# Brightside_Telemetry_RC_rev2.net
KiCad netlist of a schematic drawn in Altium Designer
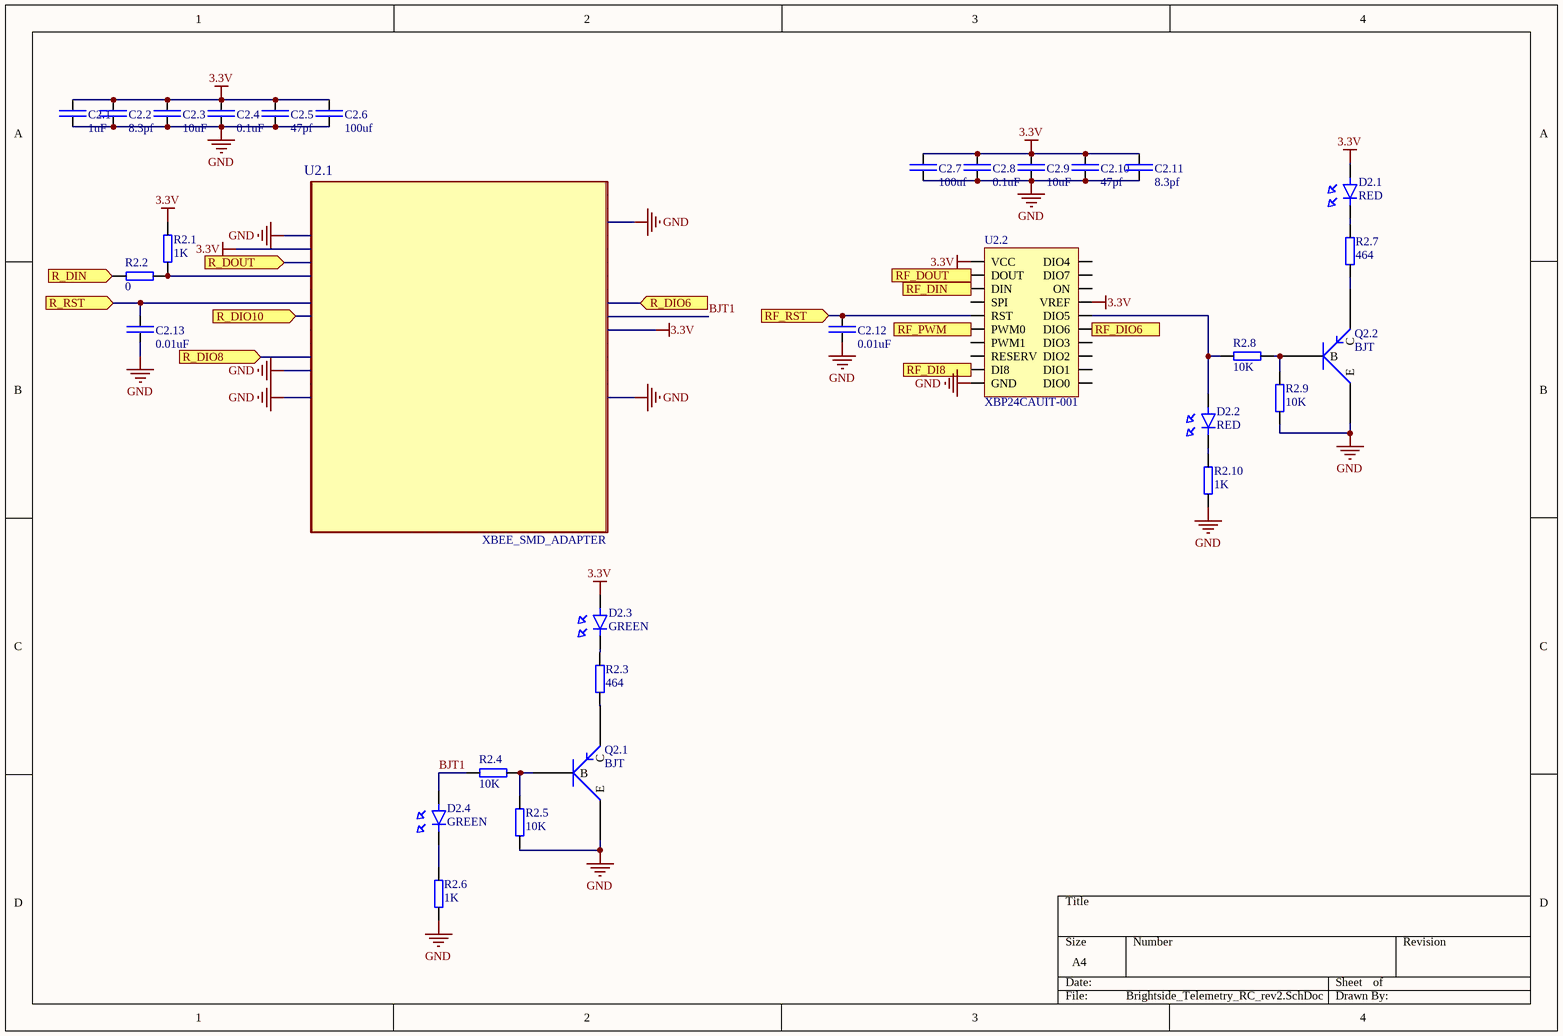
[diagram p0: Brightside_Telemetry_RC_rev2.SchDoc]

(export (version "E")
  (design (tool "Eeschema 10.0.6"))
  (components
    (comp (ref "C2.1")
      (value "1uF")
      (footprint "C0805")
      (description "Cap Ceramic 1uF 25V X7R 10% SMD 0805 125C T/R")
      (fields
        (field (name "MANUFACTURER") "Samsung")
        (field (name "MANUFACTURER PART NUMBER") "CL21B105KAFNNNE")
      )
      (libsource (lib "Capacitors") (part "CL21B105KAFNNNE"))
    )
    (comp (ref "C2.2")
      (value "8.3pf")
      (footprint "0603")
      (description "CAP CER RF 8.3PF 250V +/-0.1 PF")
      (fields
        (field (name "MANUFACTURER") "KEMET")
        (field (name "MANUFACTURER PART NUMBER") "CBR06C839BAGAC")
      )
      (libsource (lib "schem_lib") (part "CBR06C839BAGAC"))
    )
    (comp (ref "C2.3")
      (value "10uF")
      (footprint "C0805")
      (description "CAP CER 10UF 10V X5R 0805")
      (fields
        (field (name "MANUFACTURER") "Samsung")
        (field (name "MANUFACTURER PART NUMBER") "CL21B105KAFNNNE")
      )
      (libsource (lib "Capacitors") (part "C0805C106K8PACTU"))
    )
    (comp (ref "C2.4")
      (value "0.1uF")
      (footprint "0805")
      (description "Cap Ceramic 0.1uF 50V X7R 20% SMD 0805 125C Paper T/R")
      (fields
        (field (name "MANUFACTURER") "Samsung")
        (field (name "MANUFACTURER PART NUMBER") "CL21B104MBCNNNC")
      )
      (libsource (lib "Capacitors") (part "CL21B104MBCNNNC"))
    )
    (comp (ref "C2.5")
      (value "47pf")
      (footprint "0603")
      (description "CAP CER 47PF 100V C0G/NP0 0603")
      (fields
        (field (name "MANUFACTURER") "KEMET")
        (field (name "MANUFACTURER PART NUMBER") "C0603C470J1GACTU")
      )
      (libsource (lib "schem_lib") (part "C0603C470J1GACTU"))
    )
    (comp (ref "C2.6")
      (value "100uf")
      (footprint "1206")
      (description "Cap Ceramic 100uF 6.3V X5R 20% SMD 1206 85°C Embossed T/R")
      (fields
        (field (name "MANUFACTURER") "Murata")
        (field (name "MANUFACTURER PART NUMBER") "GRM21BR60G107ME15L")
      )
      (libsource (lib "schem_lib") (part "GRM21BR60G107ME15L"))
    )
    (comp (ref "C2.7")
      (value "100uf")
      (footprint "1206")
      (description "Cap Ceramic 100uF 6.3V X5R 20% SMD 1206 85°C Embossed T/R")
      (fields
        (field (name "MANUFACTURER") "Murata")
        (field (name "MANUFACTURER PART NUMBER") "GRM21BR60G107ME15L")
      )
      (libsource (lib "schem_lib") (part "GRM21BR60G107ME15L"))
    )
    (comp (ref "C2.8")
      (value "0.1uF")
      (footprint "0805")
      (description "Cap Ceramic 0.1uF 50V X7R 20% SMD 0805 125C Paper T/R")
      (fields
        (field (name "MANUFACTURER") "Samsung")
        (field (name "MANUFACTURER PART NUMBER") "CL21B104MBCNNNC")
      )
      (libsource (lib "Capacitors") (part "CL21B104MBCNNNC"))
    )
    (comp (ref "C2.9")
      (value "10uF")
      (footprint "C0805")
      (description "CAP CER 10UF 10V X5R 0805")
      (fields
        (field (name "MANUFACTURER") "Samsung")
        (field (name "MANUFACTURER PART NUMBER") "CL21B105KAFNNNE")
      )
      (libsource (lib "Capacitors") (part "C0805C106K8PACTU"))
    )
    (comp (ref "C2.10")
      (value "47pf")
      (footprint "0603")
      (description "CAP CER 47PF 100V C0G/NP0 0603")
      (fields
        (field (name "MANUFACTURER") "KEMET")
        (field (name "MANUFACTURER PART NUMBER") "C0603C470J1GACTU")
      )
      (libsource (lib "schem_lib") (part "C0603C470J1GACTU"))
    )
    (comp (ref "C2.11")
      (value "8.3pf")
      (footprint "0603")
      (description "CAP CER RF 8.3PF 250V +/-0.1 PF")
      (fields
        (field (name "MANUFACTURER") "KEMET")
        (field (name "MANUFACTURER PART NUMBER") "CBR06C839BAGAC")
      )
      (libsource (lib "schem_lib") (part "CBR06C839BAGAC"))
    )
    (comp (ref "C2.12")
      (value "0.01uF")
      (footprint "0805")
      (description "Cap Ceramic 0.01uF 100V X7R 10% SMD 0805 125C T/R")
      (fields
        (field (name "MANUFACTURER") "KEMET")
        (field (name "MANUFACTURER PART NUMBER") "C0805C103K1RAC7210")
      )
      (libsource (lib "Capacitors") (part "C0805C103K1RAC7210"))
    )
    (comp (ref "C2.13")
      (value "0.01uF")
      (footprint "0805")
      (description "Cap Ceramic 0.01uF 100V X7R 10% SMD 0805 125C T/R")
      (fields
        (field (name "MANUFACTURER") "KEMET")
        (field (name "MANUFACTURER PART NUMBER") "C0805C103K1RAC7210")
      )
      (libsource (lib "Capacitors") (part "C0805C103K1RAC7210"))
    )
    (comp (ref "D2.1")
      (value "RED")
      (footprint "0603 LED")
      (description "WURTH ELEKTRONIK - 150060RS75000 - LED, Red, 625 nm, 2 V, 30 mA, 250 mcd RoHS Compliant: Yes")
      (fields
        (field (name "MANUFACTURER") "Wurth Electronics")
        (field (name "MANUFACTURER PART NUMBER") "150060RS75000")
      )
      (libsource (lib "Indication & Control") (part "150060RS75000"))
    )
    (comp (ref "D2.2")
      (value "RED")
      (footprint "0603 LED")
      (description "WURTH ELEKTRONIK - 150060RS75000 - LED, Red, 625 nm, 2 V, 30 mA, 250 mcd RoHS Compliant: Yes")
      (fields
        (field (name "MANUFACTURER") "Wurth Electronics")
        (field (name "MANUFACTURER PART NUMBER") "150060RS75000")
      )
      (libsource (lib "Indication & Control") (part "150060RS75000"))
    )
    (comp (ref "D2.3")
      (value "GREEN")
      (footprint "0603 LED")
      (description "WURTH ELEKTRONIK - 150060VS75000 - LED, Grün, Oberflächenmontage, 603, 30 mA, 2 V, 570 nm")
      (fields
        (field (name "MANUFACTURER") "Wurth Electronics")
        (field (name "MANUFACTURER PART NUMBER") "150060VS75000")
      )
      (libsource (lib "Indication & Control") (part "150060VS75000"))
    )
    (comp (ref "D2.4")
      (value "GREEN")
      (footprint "0603 LED")
      (description "WURTH ELEKTRONIK - 150060VS75000 - LED, Grün, Oberflächenmontage, 603, 30 mA, 2 V, 570 nm")
      (fields
        (field (name "MANUFACTURER") "Wurth Electronics")
        (field (name "MANUFACTURER PART NUMBER") "150060VS75000")
      )
      (libsource (lib "Indication & Control") (part "150060VS75000"))
    )
    (comp (ref "Q2.1")
      (value "BJT")
      (footprint "SOT-23-3")
      (description "Transistor, Bipolar, Si, NPN, General Purpose, VCEO 40VDC, IC 200mA, PD 225mW, SOT-23")
      (fields
        (field (name "MANUFACTURER") "ON Semiconductor")
        (field (name "MANUFACTURER PART NUMBER") "MMBT3904LT1G")
      )
      (libsource (lib "schem_lib") (part "MMBT3904LT1G"))
    )
    (comp (ref "Q2.2")
      (value "BJT")
      (footprint "SOT-23-3")
      (description "Transistor, Bipolar, Si, NPN, General Purpose, VCEO 40VDC, IC 200mA, PD 225mW, SOT-23")
      (fields
        (field (name "MANUFACTURER") "ON Semiconductor")
        (field (name "MANUFACTURER PART NUMBER") "MMBT3904LT1G")
      )
      (libsource (lib "schem_lib") (part "MMBT3904LT1G"))
    )
    (comp (ref "R2.1")
      (value "1K")
      (footprint "R0805")
      (description "RES SMD 1K OHM 1% 1/8W 0805")
      (fields
        (field (name "MANUFACTURER") "Panasonic")
        (field (name "MANUFACTURER PART NUMBER") "ERJ6ENF1001V")
      )
      (libsource (lib "Resistors") (part "ERJ6ENF1001V"))
    )
    (comp (ref "R2.2")
      (value "0")
      (footprint "0805")
      (fields
        (field (name "MANUFACTURER") "Stackpole Electronics")
        (field (name "MANUFACTURER PART NUMBER") "RMCF0805ZT0R00")
      )
      (libsource (lib "Resistors") (part "RMCF0805ZT0R00"))
    )
    (comp (ref "R2.3")
      (value "464")
      (footprint "R0805")
      (description "RES SMD 464 OHM 1% 1/8W 0805")
      (libsource (lib "Resistors") (part "ERJ6ENF4640V"))
    )
    (comp (ref "R2.4")
      (value "10K")
      (footprint "R0805")
      (description "RES SMD 10K OHM 1% 1/8W 0805")
      (fields (field (name "MANUFACTURER") "Yageo") (field (name "MANUFACTURER PART NUMBER") "ERJ-6ENF1002V"))
      (libsource (lib "Resistors") (part "ERJ6ENF1002V"))
    )
    (comp (ref "R2.5")
      (value "10K")
      (footprint "R0805")
      (description "RES SMD 10K OHM 1% 1/8W 0805")
      (fields (field (name "MANUFACTURER") "Yageo") (field (name "MANUFACTURER PART NUMBER") "ERJ-6ENF1002V"))
      (libsource (lib "Resistors") (part "ERJ6ENF1002V"))
    )
    (comp (ref "R2.6")
      (value "1K")
      (footprint "R0805")
      (description "RES SMD 1K OHM 1% 1/8W 0805")
      (fields
        (field (name "MANUFACTURER") "Panasonic")
        (field (name "MANUFACTURER PART NUMBER") "ERJ6ENF1001V")
      )
      (libsource (lib "Resistors") (part "ERJ6ENF1001V"))
    )
    (comp (ref "R2.7")
      (value "464")
      (footprint "R0805")
      (description "RES SMD 464 OHM 1% 1/8W 0805")
      (libsource (lib "Resistors") (part "ERJ6ENF4640V"))
    )
    (comp (ref "R2.8")
      (value "10K")
      (footprint "R0805")
      (description "RES SMD 10K OHM 1% 1/8W 0805")
      (fields (field (name "MANUFACTURER") "Yageo") (field (name "MANUFACTURER PART NUMBER") "ERJ-6ENF1002V"))
      (libsource (lib "Resistors") (part "ERJ6ENF1002V"))
    )
    (comp (ref "R2.9")
      (value "10K")
      (footprint "R0805")
      (description "RES SMD 10K OHM 1% 1/8W 0805")
      (fields (field (name "MANUFACTURER") "Yageo") (field (name "MANUFACTURER PART NUMBER") "ERJ-6ENF1002V"))
      (libsource (lib "Resistors") (part "ERJ6ENF1002V"))
    )
    (comp (ref "R2.10")
      (value "1K")
      (footprint "R0805")
      (description "RES SMD 1K OHM 1% 1/8W 0805")
      (fields
        (field (name "MANUFACTURER") "Panasonic")
        (field (name "MANUFACTURER PART NUMBER") "ERJ6ENF1001V")
      )
      (libsource (lib "Resistors") (part "ERJ6ENF1001V"))
    )
    (comp (ref "U2.1")
      (value "XBEE_SMD_ADAPTER")
      (footprint "XBEE_RF_ADAPT")
      (fields (field (name "LIBRARYNAME") "UBCSolar"))
      (libsource (lib "UBCSolar") (part "XBEE_SMD_ADAPTER"))
    )
    (comp (ref "U2.2")
      (value "XBP24CAUIT-001")
      (footprint "XBEE_RF")
      (description "Rf Transceiver Module, 2.4GHZ, -101DBM")
      (fields (field (name "MANUFACTURER") "Digi International"))
      (libsource (lib "schem_lib") (part "XBP24CAUIT-001"))
    )
  )
  (nets
    (net (code "1") (name "/BJT1") (class "Default")
      (node (ref "D2.4") (pin "2") (pinfunction "2_2") (pintype "passive"))
      (node (ref "R2.4") (pin "1") (pinfunction "1_1") (pintype "passive"))
      (node (ref "U2.1") (pin "28") (pinfunction "P$28_28") (pintype "bidirectional"))
    )
    (net (code "2") (name "/RF_DI8") (class "Default")
      (node (ref "U2.2") (pin "9") (pinfunction "DI8_9") (pintype "passive"))
    )
    (net (code "3") (name "/RF_DIN") (class "Default")
      (node (ref "U2.2") (pin "3") (pinfunction "DIN_3") (pintype "passive"))
    )
    (net (code "5") (name "/RF_DIO6") (class "Default")
      (node (ref "U2.2") (pin "16") (pinfunction "DIO6_16") (pintype "passive"))
    )
    (net (code "6") (name "/RF_DOUT") (class "Default")
      (node (ref "U2.2") (pin "2") (pinfunction "DOUT_2") (pintype "passive"))
    )
    (net (code "7") (name "/RF_PWM") (class "Default")
      (node (ref "U2.2") (pin "6") (pinfunction "PWM0_6") (pintype "passive"))
    )
    (net (code "8") (name "/RF_RST") (class "Default")
      (node (ref "C2.12") (pin "1") (pinfunction "1_1") (pintype "passive"))
      (node (ref "U2.2") (pin "5") (pinfunction "RST_5") (pintype "passive"))
    )
    (net (code "9") (name "/R_DIN") (class "Default")
      (node (ref "R2.2") (pin "1") (pinfunction "1_1") (pintype "passive"))
    )
    (net (code "10") (name "/R_DIO6") (class "Default")
      (node (ref "U2.1") (pin "29") (pinfunction "P$29_29") (pintype "bidirectional"))
    )
    (net (code "11") (name "/R_DIO8") (class "Default")
      (node (ref "U2.1") (pin "10") (pinfunction "P$10_10") (pintype "bidirectional"))
    )
    (net (code "12") (name "/R_DIO10") (class "Default")
      (node (ref "U2.1") (pin "7") (pinfunction "P$7_7") (pintype "bidirectional"))
    )
    (net (code "13") (name "/R_DOUT") (class "Default")
      (node (ref "U2.1") (pin "3") (pinfunction "P$3_3") (pintype "bidirectional"))
    )
    (net (code "14") (name "/R_RST") (class "Default")
      (node (ref "C2.13") (pin "2") (pinfunction "2_2") (pintype "passive"))
      (node (ref "U2.1") (pin "6") (pinfunction "P$6_6") (pintype "bidirectional"))
    )
    (net (code "15") (name "3.3V") (class "Default")
      (node (ref "C2.1") (pin "2") (pinfunction "2_2") (pintype "passive"))
      (node (ref "C2.10") (pin "2") (pinfunction "2_2") (pintype "passive"))
      (node (ref "C2.11") (pin "2") (pinfunction "2_2") (pintype "passive"))
      (node (ref "C2.2") (pin "2") (pinfunction "2_2") (pintype "passive"))
      (node (ref "C2.3") (pin "2") (pinfunction "2_2") (pintype "passive"))
      (node (ref "C2.4") (pin "2") (pinfunction "2_2") (pintype "passive"))
      (node (ref "C2.5") (pin "1") (pinfunction "1_1") (pintype "passive"))
      (node (ref "C2.6") (pin "2") (pinfunction "2_2") (pintype "passive"))
      (node (ref "C2.7") (pin "2") (pinfunction "2_2") (pintype "passive"))
      (node (ref "C2.8") (pin "1") (pinfunction "1_1") (pintype "passive"))
      (node (ref "C2.9") (pin "2") (pinfunction "2_2") (pintype "passive"))
      (node (ref "D2.1") (pin "2") (pinfunction "2_2") (pintype "passive"))
      (node (ref "D2.3") (pin "2") (pinfunction "2_2") (pintype "passive"))
      (node (ref "R2.1") (pin "2") (pinfunction "2_2") (pintype "passive"))
      (node (ref "U2.1") (pin "2") (pinfunction "P$2_2") (pintype "bidirectional"))
      (node (ref "U2.1") (pin "27") (pinfunction "P$27_27") (pintype "bidirectional"))
      (node (ref "U2.2") (pin "1") (pinfunction "VCC_1") (pintype "passive"))
      (node (ref "U2.2") (pin "14") (pinfunction "VREF_14") (pintype "passive"))
    )
    (net (code "16") (name "GND") (class "Default")
      (node (ref "C2.1") (pin "1") (pinfunction "1_1") (pintype "passive"))
      (node (ref "C2.10") (pin "1") (pinfunction "1_1") (pintype "passive"))
      (node (ref "C2.11") (pin "1") (pinfunction "1_1") (pintype "passive"))
      (node (ref "C2.12") (pin "2") (pinfunction "2_2") (pintype "passive"))
      (node (ref "C2.13") (pin "1") (pinfunction "1_1") (pintype "passive"))
      (node (ref "C2.2") (pin "1") (pinfunction "1_1") (pintype "passive"))
      (node (ref "C2.3") (pin "1") (pinfunction "1_1") (pintype "passive"))
      (node (ref "C2.4") (pin "1") (pinfunction "1_1") (pintype "passive"))
      (node (ref "C2.5") (pin "2") (pinfunction "2_2") (pintype "passive"))
      (node (ref "C2.6") (pin "1") (pinfunction "1_1") (pintype "passive"))
      (node (ref "C2.7") (pin "1") (pinfunction "1_1") (pintype "passive"))
      (node (ref "C2.8") (pin "2") (pinfunction "2_2") (pintype "passive"))
      (node (ref "C2.9") (pin "1") (pinfunction "1_1") (pintype "passive"))
      (node (ref "Q2.1") (pin "3") (pinfunction "E_3") (pintype "passive"))
      (node (ref "Q2.2") (pin "3") (pinfunction "E_3") (pintype "passive"))
      (node (ref "R2.10") (pin "1") (pinfunction "1_1") (pintype "passive"))
      (node (ref "R2.5") (pin "1") (pinfunction "1_1") (pintype "passive"))
      (node (ref "R2.6") (pin "1") (pinfunction "1_1") (pintype "passive"))
      (node (ref "R2.9") (pin "1") (pinfunction "1_1") (pintype "passive"))
      (node (ref "U2.1") (pin "1") (pinfunction "P$1_1") (pintype "bidirectional"))
      (node (ref "U2.1") (pin "11") (pinfunction "P$11_11") (pintype "bidirectional"))
      (node (ref "U2.1") (pin "13") (pinfunction "P$13_13") (pintype "bidirectional"))
      (node (ref "U2.1") (pin "22") (pinfunction "P$22_22") (pintype "bidirectional"))
      (node (ref "U2.1") (pin "35") (pinfunction "P$35_35") (pintype "bidirectional"))
      (node (ref "U2.2") (pin "10") (pinfunction "GND_10") (pintype "passive"))
    )
    (net (code "17") (name "Net-(D2.1-Pad1)") (class "Default")
      (node (ref "D2.1") (pin "1") (pinfunction "1_1") (pintype "passive"))
      (node (ref "R2.7") (pin "2") (pinfunction "2_2") (pintype "passive"))
    )
    (net (code "18") (name "Net-(D2.2-Pad1)") (class "Default")
      (node (ref "D2.2") (pin "1") (pinfunction "1_1") (pintype "passive"))
      (node (ref "R2.10") (pin "2") (pinfunction "2_2") (pintype "passive"))
    )
    (net (code "19") (name "Net-(D2.3-Pad1)") (class "Default")
      (node (ref "D2.3") (pin "1") (pinfunction "1_1") (pintype "passive"))
      (node (ref "R2.3") (pin "2") (pinfunction "2_2") (pintype "passive"))
    )
    (net (code "20") (name "Net-(D2.4-Pad1)") (class "Default")
      (node (ref "D2.4") (pin "1") (pinfunction "1_1") (pintype "passive"))
      (node (ref "R2.6") (pin "2") (pinfunction "2_2") (pintype "passive"))
    )
    (net (code "21") (name "Net-(Q2.1-B)") (class "Default")
      (node (ref "Q2.1") (pin "1") (pinfunction "B_1") (pintype "passive"))
      (node (ref "R2.4") (pin "2") (pinfunction "2_2") (pintype "passive"))
      (node (ref "R2.5") (pin "2") (pinfunction "2_2") (pintype "passive"))
    )
    (net (code "22") (name "Net-(Q2.1-C)") (class "Default")
      (node (ref "Q2.1") (pin "2") (pinfunction "C_2") (pintype "passive"))
      (node (ref "R2.3") (pin "1") (pinfunction "1_1") (pintype "passive"))
    )
    (net (code "23") (name "Net-(Q2.2-B)") (class "Default")
      (node (ref "Q2.2") (pin "1") (pinfunction "B_1") (pintype "passive"))
      (node (ref "R2.8") (pin "2") (pinfunction "2_2") (pintype "passive"))
      (node (ref "R2.9") (pin "2") (pinfunction "2_2") (pintype "passive"))
    )
    (net (code "24") (name "Net-(Q2.2-C)") (class "Default")
      (node (ref "Q2.2") (pin "2") (pinfunction "C_2") (pintype "passive"))
      (node (ref "R2.7") (pin "1") (pinfunction "1_1") (pintype "passive"))
    )
    (net (code "25") (name "Net-(U2.1-P$4)") (class "Default")
      (node (ref "R2.1") (pin "1") (pinfunction "1_1") (pintype "passive"))
      (node (ref "R2.2") (pin "2") (pinfunction "2_2") (pintype "passive"))
      (node (ref "U2.1") (pin "4") (pinfunction "P$4_4") (pintype "bidirectional"))
    )
    (net (code "26") (name "Net-(U2.2-DIO5)") (class "Default")
      (node (ref "D2.2") (pin "2") (pinfunction "2_2") (pintype "passive"))
      (node (ref "R2.8") (pin "1") (pinfunction "1_1") (pintype "passive"))
      (node (ref "U2.2") (pin "15") (pinfunction "DIO5_15") (pintype "passive"))
    )
    (net (code "27") (name "unconnected-(U2.1-P$5-Pad5)") (class "Default")
      (node (ref "U2.1") (pin "5") (pinfunction "P$5_5") (pintype "bidirectional"))
    )
    (net (code "28") (name "unconnected-(U2.1-P$8-Pad8)") (class "Default")
      (node (ref "U2.1") (pin "8") (pinfunction "P$8_8") (pintype "bidirectional"))
    )
    (net (code "29") (name "unconnected-(U2.1-P$9-Pad9)") (class "Default")
      (node (ref "U2.1") (pin "9") (pinfunction "P$9_9") (pintype "bidirectional"))
    )
    (net (code "30") (name "unconnected-(U2.1-P$12-Pad12)") (class "Default")
      (node (ref "U2.1") (pin "12") (pinfunction "P$12_12") (pintype "bidirectional"))
    )
    (net (code "31") (name "unconnected-(U2.1-P$14-Pad14)") (class "Default")
      (node (ref "U2.1") (pin "14") (pinfunction "P$14_14") (pintype "bidirectional"))
    )
    (net (code "32") (name "unconnected-(U2.1-P$15-Pad15)") (class "Default")
      (node (ref "U2.1") (pin "15") (pinfunction "P$15_15") (pintype "bidirectional"))
    )
    (net (code "33") (name "unconnected-(U2.1-P$16-Pad16)") (class "Default")
      (node (ref "U2.1") (pin "16") (pinfunction "P$16_16") (pintype "bidirectional"))
    )
    (net (code "34") (name "unconnected-(U2.1-P$17-Pad17)") (class "Default")
      (node (ref "U2.1") (pin "17") (pinfunction "P$17_17") (pintype "bidirectional"))
    )
    (net (code "35") (name "unconnected-(U2.1-P$18-Pad18)") (class "Default")
      (node (ref "U2.1") (pin "18") (pinfunction "P$18_18") (pintype "bidirectional"))
    )
    (net (code "36") (name "unconnected-(U2.1-P$19-Pad19)") (class "Default")
      (node (ref "U2.1") (pin "19") (pinfunction "P$19_19") (pintype "bidirectional"))
    )
    (net (code "37") (name "unconnected-(U2.1-P$20-Pad20)") (class "Default")
      (node (ref "U2.1") (pin "20") (pinfunction "P$20_20") (pintype "bidirectional"))
    )
    (net (code "38") (name "unconnected-(U2.1-P$21-Pad21)") (class "Default")
      (node (ref "U2.1") (pin "21") (pinfunction "P$21_21") (pintype "bidirectional"))
    )
    (net (code "39") (name "unconnected-(U2.1-P$23-Pad23)") (class "Default")
      (node (ref "U2.1") (pin "23") (pinfunction "P$23_23") (pintype "bidirectional"))
    )
    (net (code "40") (name "unconnected-(U2.1-P$24-Pad24)") (class "Default")
      (node (ref "U2.1") (pin "24") (pinfunction "P$24_24") (pintype "bidirectional"))
    )
    (net (code "41") (name "unconnected-(U2.1-P$25-Pad25)") (class "Default")
      (node (ref "U2.1") (pin "25") (pinfunction "P$25_25") (pintype "bidirectional"))
    )
    (net (code "42") (name "unconnected-(U2.1-P$26-Pad26)") (class "Default")
      (node (ref "U2.1") (pin "26") (pinfunction "P$26_26") (pintype "bidirectional"))
    )
    (net (code "43") (name "unconnected-(U2.1-P$30-Pad30)") (class "Default")
      (node (ref "U2.1") (pin "30") (pinfunction "P$30_30") (pintype "bidirectional"))
    )
    (net (code "44") (name "unconnected-(U2.1-P$31-Pad31)") (class "Default")
      (node (ref "U2.1") (pin "31") (pinfunction "P$31_31") (pintype "bidirectional"))
    )
    (net (code "45") (name "unconnected-(U2.1-P$32-Pad32)") (class "Default")
      (node (ref "U2.1") (pin "32") (pinfunction "P$32_32") (pintype "bidirectional"))
    )
    (net (code "46") (name "unconnected-(U2.1-P$33-Pad33)") (class "Default")
      (node (ref "U2.1") (pin "33") (pinfunction "P$33_33") (pintype "bidirectional"))
    )
    (net (code "47") (name "unconnected-(U2.1-P$34-Pad34)") (class "Default")
      (node (ref "U2.1") (pin "34") (pinfunction "P$34_34") (pintype "bidirectional"))
    )
    (net (code "48") (name "unconnected-(U2.1-P$36-Pad36)") (class "Default")
      (node (ref "U2.1") (pin "36") (pinfunction "P$36_36") (pintype "bidirectional"))
    )
    (net (code "49") (name "unconnected-(U2.1-P$37-Pad37)") (class "Default")
      (node (ref "U2.1") (pin "37") (pinfunction "P$37_37") (pintype "bidirectional"))
    )
    (net (code "50") (name "unconnected-(U2.2-DIO0-Pad20)") (class "Default")
      (node (ref "U2.2") (pin "20") (pinfunction "DIO0_20") (pintype "passive"))
    )
    (net (code "51") (name "unconnected-(U2.2-DIO1-Pad19)") (class "Default")
      (node (ref "U2.2") (pin "19") (pinfunction "DIO1_19") (pintype "passive"))
    )
    (net (code "52") (name "unconnected-(U2.2-DIO2-Pad18)") (class "Default")
      (node (ref "U2.2") (pin "18") (pinfunction "DIO2_18") (pintype "passive"))
    )
    (net (code "53") (name "unconnected-(U2.2-DIO3-Pad17)") (class "Default")
      (node (ref "U2.2") (pin "17") (pinfunction "DIO3_17") (pintype "passive"))
    )
    (net (code "54") (name "unconnected-(U2.2-DIO4-Pad11)") (class "Default")
      (node (ref "U2.2") (pin "11") (pinfunction "DIO4_11") (pintype "passive"))
    )
    (net (code "55") (name "unconnected-(U2.2-DIO7-Pad12)") (class "Default")
      (node (ref "U2.2") (pin "12") (pinfunction "DIO7_12") (pintype "passive"))
    )
    (net (code "56") (name "unconnected-(U2.2-ON-Pad13)") (class "Default")
      (node (ref "U2.2") (pin "13") (pinfunction "ON_13") (pintype "passive"))
    )
    (net (code "57") (name "unconnected-(U2.2-PWM1-Pad7)") (class "Default")
      (node (ref "U2.2") (pin "7") (pinfunction "PWM1_7") (pintype "passive"))
    )
    (net (code "58") (name "unconnected-(U2.2-RESERV-Pad8)") (class "Default")
      (node (ref "U2.2") (pin "8") (pinfunction "RESERV_8") (pintype "passive"))
    )
    (net (code "59") (name "unconnected-(U2.2-SPI-Pad4)") (class "Default")
      (node (ref "U2.2") (pin "4") (pinfunction "SPI_4") (pintype "passive"))
    )
  )
)
